# ZYNQ_DDR3.net
KiCad netlist of a schematic drawn in Altium Designer
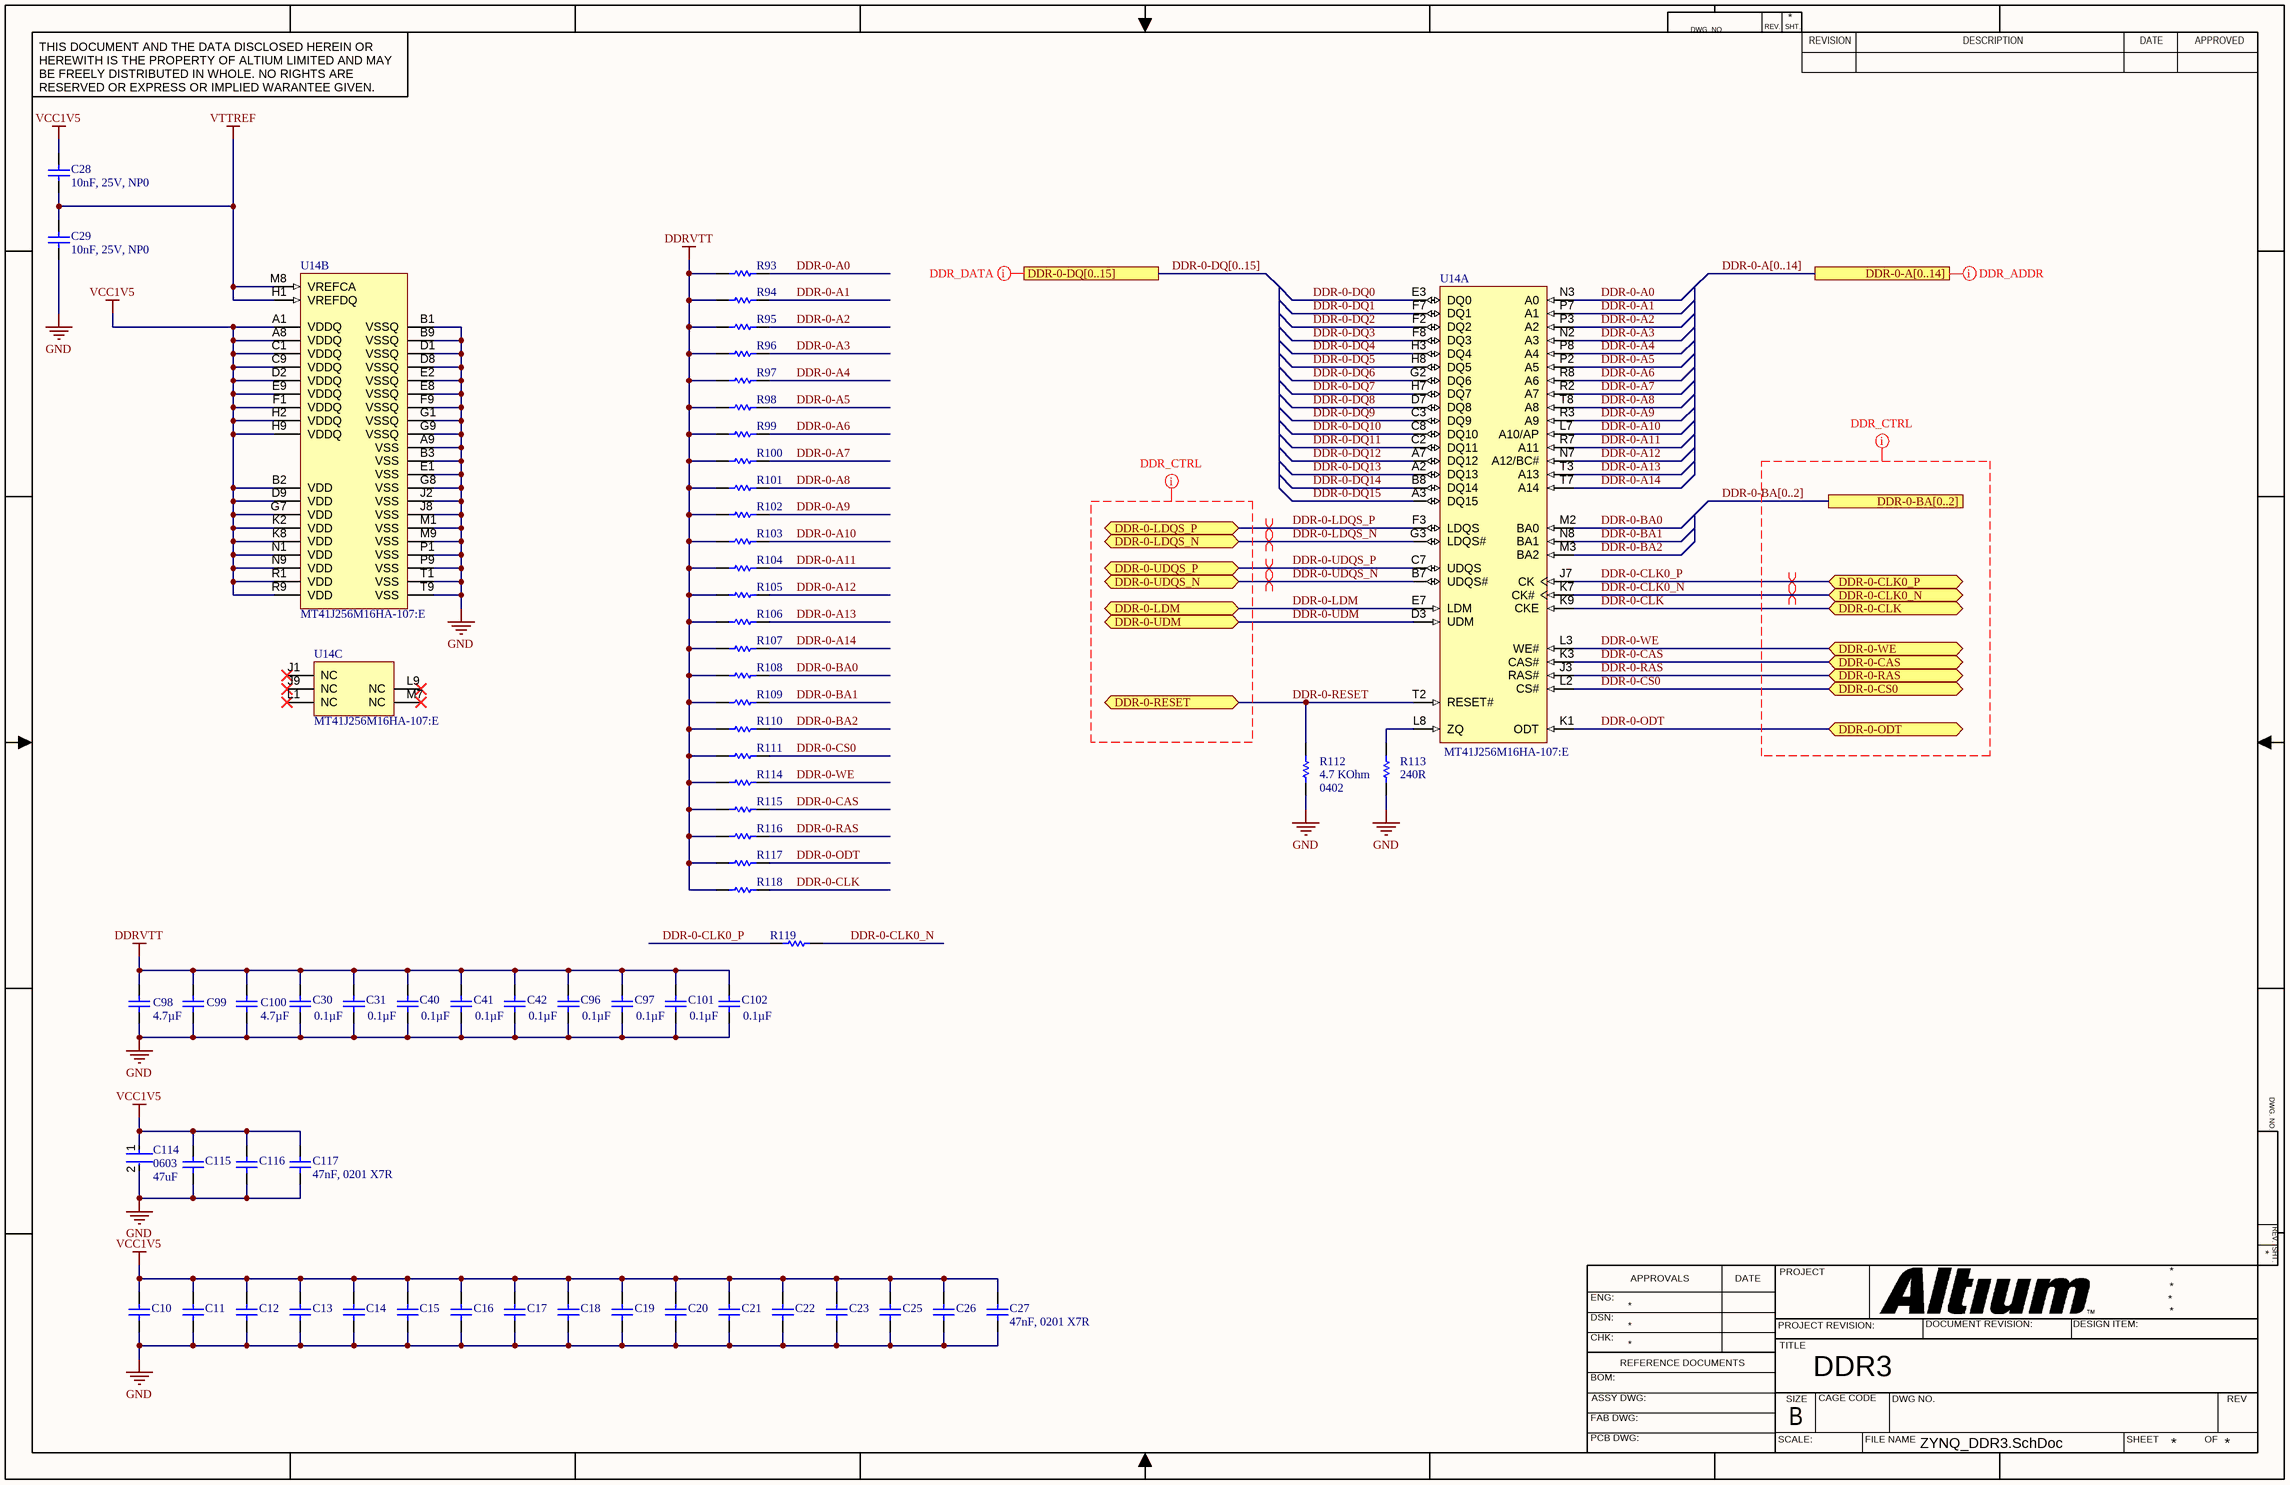
[diagram p0: ZYNQ_DDR3.SchDoc]

(export (version "E")
  (design (tool "Eeschema 10.0.6"))
  (components
    (comp (ref "C10")
      (value "~")
      (footprint "CAP0201i")
      (description "0201, 47nF, 10%, 25V, X7R")
      (libsource (lib "AmpherLib") (part "Cap_47nF_X7R_0201"))
    )
    (comp (ref "C11")
      (value "~")
      (footprint "CAP0201i")
      (description "0201, 47nF, 10%, 25V, X7R")
      (libsource (lib "AmpherLib") (part "Cap_47nF_X7R_0201"))
    )
    (comp (ref "C12")
      (value "~")
      (footprint "CAP0201i")
      (description "0201, 47nF, 10%, 25V, X7R")
      (libsource (lib "AmpherLib") (part "Cap_47nF_X7R_0201"))
    )
    (comp (ref "C13")
      (value "~")
      (footprint "CAP0201i")
      (description "0201, 47nF, 10%, 25V, X7R")
      (libsource (lib "AmpherLib") (part "Cap_47nF_X7R_0201"))
    )
    (comp (ref "C14")
      (value "~")
      (footprint "CAP0201i")
      (description "0201, 47nF, 10%, 25V, X7R")
      (libsource (lib "AmpherLib") (part "Cap_47nF_X7R_0201"))
    )
    (comp (ref "C15")
      (value "~")
      (footprint "CAP0201i")
      (description "0201, 47nF, 10%, 25V, X7R")
      (libsource (lib "AmpherLib") (part "Cap_47nF_X7R_0201"))
    )
    (comp (ref "C16")
      (value "~")
      (footprint "CAP0201i")
      (description "0201, 47nF, 10%, 25V, X7R")
      (libsource (lib "AmpherLib") (part "Cap_47nF_X7R_0201"))
    )
    (comp (ref "C17")
      (value "~")
      (footprint "CAP0201i")
      (description "0201, 47nF, 10%, 25V, X7R")
      (libsource (lib "AmpherLib") (part "Cap_47nF_X7R_0201"))
    )
    (comp (ref "C18")
      (value "~")
      (footprint "CAP0201i")
      (description "0201, 47nF, 10%, 25V, X7R")
      (libsource (lib "AmpherLib") (part "Cap_47nF_X7R_0201"))
    )
    (comp (ref "C19")
      (value "~")
      (footprint "CAP0201i")
      (description "0201, 47nF, 10%, 25V, X7R")
      (libsource (lib "AmpherLib") (part "Cap_47nF_X7R_0201"))
    )
    (comp (ref "C20")
      (value "~")
      (footprint "CAP0201i")
      (description "0201, 47nF, 10%, 25V, X7R")
      (libsource (lib "AmpherLib") (part "Cap_47nF_X7R_0201"))
    )
    (comp (ref "C21")
      (value "~")
      (footprint "CAP0201i")
      (description "0201, 47nF, 10%, 25V, X7R")
      (libsource (lib "AmpherLib") (part "Cap_47nF_X7R_0201"))
    )
    (comp (ref "C22")
      (value "~")
      (footprint "CAP0201i")
      (description "0201, 47nF, 10%, 25V, X7R")
      (libsource (lib "AmpherLib") (part "Cap_47nF_X7R_0201"))
    )
    (comp (ref "C23")
      (value "~")
      (footprint "CAP0201i")
      (description "0201, 47nF, 10%, 25V, X7R")
      (libsource (lib "AmpherLib") (part "Cap_47nF_X7R_0201"))
    )
    (comp (ref "C25")
      (value "~")
      (footprint "CAP0201i")
      (description "0201, 47nF, 10%, 25V, X7R")
      (libsource (lib "AmpherLib") (part "Cap_47nF_X7R_0201"))
    )
    (comp (ref "C26")
      (value "~")
      (footprint "CAP0201i")
      (description "0201, 47nF, 10%, 25V, X7R")
      (libsource (lib "AmpherLib") (part "Cap_47nF_X7R_0201"))
    )
    (comp (ref "C27")
      (value "47nF, 0201 X7R")
      (footprint "CAP0201i")
      (description "0201, 47nF, 10%, 25V, X7R")
      (libsource (lib "AmpherLib") (part "Cap_47nF_X7R_0201"))
    )
    (comp (ref "C28")
      (value "10nF, 25V, NP0")
      (footprint "CAP0402i")
      (description "0402,10nF,5%,25V,NP0")
      (fields (field (name "PART NUMBER") "GRM1555C1E103JE01J") (field (name "MANUFACTURER") "Murata"))
      (libsource (lib "AmpherLib") (part "Cap_10nF_25V_NP0_0402"))
    )
    (comp (ref "C29")
      (value "10nF, 25V, NP0")
      (footprint "CAP0402i")
      (description "0402,10nF,5%,25V,NP0")
      (fields (field (name "PART NUMBER") "GRM1555C1E103JE01J") (field (name "MANUFACTURER") "Murata"))
      (libsource (lib "AmpherLib") (part "Cap_10nF_25V_NP0_0402"))
    )
    (comp (ref "C30")
      (value "0.1µF")
      (footprint "CAP0402i")
      (description "0402, 0.1uF, 10%,  50V, X7R")
      (fields
        (field (name "PART NUMBER") "C1005X7R1H104K050BE")
        (field (name "VOLTAGE") "50V")
        (field (name "CAPACITANCE") "0.1µF")
      )
      (libsource (lib "AmpherLib") (part "Cap_0.1uF_50V_X7R_0402"))
    )
    (comp (ref "C31")
      (value "0.1µF")
      (footprint "CAP0402i")
      (description "0402, 0.1uF, 10%,  50V, X7R")
      (fields
        (field (name "PART NUMBER") "C1005X7R1H104K050BE")
        (field (name "VOLTAGE") "50V")
        (field (name "CAPACITANCE") "0.1µF")
      )
      (libsource (lib "AmpherLib") (part "Cap_0.1uF_50V_X7R_0402"))
    )
    (comp (ref "C40")
      (value "0.1µF")
      (footprint "CAP0402i")
      (description "0402, 0.1uF, 10%,  50V, X7R")
      (fields
        (field (name "PART NUMBER") "C1005X7R1H104K050BE")
        (field (name "VOLTAGE") "50V")
        (field (name "CAPACITANCE") "0.1µF")
      )
      (libsource (lib "AmpherLib") (part "Cap_0.1uF_50V_X7R_0402"))
    )
    (comp (ref "C41")
      (value "0.1µF")
      (footprint "CAP0402i")
      (description "0402, 0.1uF, 10%,  50V, X7R")
      (fields
        (field (name "PART NUMBER") "C1005X7R1H104K050BE")
        (field (name "VOLTAGE") "50V")
        (field (name "CAPACITANCE") "0.1µF")
      )
      (libsource (lib "AmpherLib") (part "Cap_0.1uF_50V_X7R_0402"))
    )
    (comp (ref "C42")
      (value "0.1µF")
      (footprint "CAP0402i")
      (description "0402, 0.1uF, 10%,  50V, X7R")
      (fields
        (field (name "PART NUMBER") "C1005X7R1H104K050BE")
        (field (name "VOLTAGE") "50V")
        (field (name "CAPACITANCE") "0.1µF")
      )
      (libsource (lib "AmpherLib") (part "Cap_0.1uF_50V_X7R_0402"))
    )
    (comp (ref "C96")
      (value "0.1µF")
      (footprint "CAP0402i")
      (description "0402, 0.1uF, 10%,  50V, X7R")
      (fields
        (field (name "PART NUMBER") "C1005X7R1H104K050BE")
        (field (name "VOLTAGE") "50V")
        (field (name "CAPACITANCE") "0.1µF")
      )
      (libsource (lib "AmpherLib") (part "Cap_0.1uF_50V_X7R_0402"))
    )
    (comp (ref "C97")
      (value "0.1µF")
      (footprint "CAP0402i")
      (description "0402, 0.1uF, 10%,  50V, X7R")
      (fields
        (field (name "PART NUMBER") "C1005X7R1H104K050BE")
        (field (name "VOLTAGE") "50V")
        (field (name "CAPACITANCE") "0.1µF")
      )
      (libsource (lib "AmpherLib") (part "Cap_0.1uF_50V_X7R_0402"))
    )
    (comp (ref "C98")
      (value "4.7µF")
      (footprint "CAP0402i")
      (description "CAP CER 4.7UF 10V X5R 0402")
      (fields
        (field (name "TOLERANCE") "10%")
        (field (name "CAPACITANCE") "4.7µF")
        (field (name "PART NUMBER") "C1005X5R1A475K050BC")
      )
      (libsource (lib "AmpherLib") (part "Cap_4.7uF_10V_10%_0402"))
    )
    (comp (ref "C99")
      (value "4.7µF")
      (footprint "CAP0402i")
      (description "CAP CER 4.7UF 10V X5R 0402")
      (fields (field (name "TOLERANCE") "10%") (field (name "PART NUMBER") "C1005X5R1A475K050BC"))
      (libsource (lib "AmpherLib") (part "Cap_4.7uF_10V_10%_0402"))
    )
    (comp (ref "C100")
      (value "4.7µF")
      (footprint "CAP0402i")
      (description "CAP CER 4.7UF 10V X5R 0402")
      (fields
        (field (name "TOLERANCE") "10%")
        (field (name "CAPACITANCE") "4.7µF")
        (field (name "PART NUMBER") "C1005X5R1A475K050BC")
      )
      (libsource (lib "AmpherLib") (part "Cap_4.7uF_10V_10%_0402"))
    )
    (comp (ref "C101")
      (value "0.1µF")
      (footprint "CAP0402i")
      (description "0402, 0.1uF, 10%,  50V, X7R")
      (fields
        (field (name "PART NUMBER") "C1005X7R1H104K050BE")
        (field (name "VOLTAGE") "50V")
        (field (name "CAPACITANCE") "0.1µF")
      )
      (libsource (lib "AmpherLib") (part "Cap_0.1uF_50V_X7R_0402"))
    )
    (comp (ref "C102")
      (value "0.1µF")
      (footprint "CAP0402i")
      (description "0402, 0.1uF, 10%,  50V, X7R")
      (fields
        (field (name "PART NUMBER") "C1005X7R1H104K050BE")
        (field (name "VOLTAGE") "50V")
        (field (name "CAPACITANCE") "0.1µF")
      )
      (libsource (lib "AmpherLib") (part "Cap_0.1uF_50V_X7R_0402"))
    )
    (comp (ref "C114")
      (value "GRM188R60J476ME15D")
      (footprint "FP-GRM188-0_2-IPC_B")
      (description "Chip Multilayer Ceramic Capacitors for General Purpose, 0603, 47uF, X5R, 15%, 20%, 6.3V")
      (fields
        (field (name "CASE CODE (IMPERIAL)") "0603")
        (field (name "CAPACITANCE") "47uF")
        (field (name "TOLERANCE") "20%")
      )
      (libsource (lib "Altium Content Vault") (part "11868f565c42a9108669ba33697ecf6"))
    )
    (comp (ref "C115")
      (value "4.7µF")
      (footprint "CAP0402i")
      (description "CAP CER 4.7UF 10V X5R 0402")
      (fields (field (name "TOLERANCE") "10%") (field (name "PART NUMBER") "C1005X5R1A475K050BC"))
      (libsource (lib "AmpherLib") (part "Cap_4.7uF_10V_10%_0402"))
    )
    (comp (ref "C116")
      (value "~")
      (footprint "CAP0201i")
      (description "0201, 47nF, 10%, 25V, X7R")
      (libsource (lib "AmpherLib") (part "Cap_47nF_X7R_0201"))
    )
    (comp (ref "C117")
      (value "47nF, 0201 X7R")
      (footprint "CAP0201i")
      (description "0201, 47nF, 10%, 25V, X7R")
      (libsource (lib "AmpherLib") (part "Cap_47nF_X7R_0201"))
    )
    (comp (ref "R93")
      (value "ERJ2RKF33R0X")
      (footprint "RESC1005X40X25LL05T05")
      (fields (field (name "MANUFACTURER") "Panasonic"))
      (libsource (lib "Altium Content Vault") (part "RES"))
    )
    (comp (ref "R94")
      (value "ERJ2RKF33R0X")
      (footprint "RESC1005X40X25LL05T05")
      (fields (field (name "MANUFACTURER") "Panasonic"))
      (libsource (lib "Altium Content Vault") (part "RES"))
    )
    (comp (ref "R95")
      (value "ERJ2RKF33R0X")
      (footprint "RESC1005X40X25LL05T05")
      (fields (field (name "MANUFACTURER") "Panasonic"))
      (libsource (lib "Altium Content Vault") (part "RES"))
    )
    (comp (ref "R96")
      (value "ERJ2RKF33R0X")
      (footprint "RESC1005X40X25LL05T05")
      (fields (field (name "MANUFACTURER") "Panasonic"))
      (libsource (lib "Altium Content Vault") (part "RES"))
    )
    (comp (ref "R97")
      (value "ERJ2RKF33R0X")
      (footprint "RESC1005X40X25LL05T05")
      (fields (field (name "MANUFACTURER") "Panasonic"))
      (libsource (lib "Altium Content Vault") (part "RES"))
    )
    (comp (ref "R98")
      (value "ERJ2RKF33R0X")
      (footprint "RESC1005X40X25LL05T05")
      (fields (field (name "MANUFACTURER") "Panasonic"))
      (libsource (lib "Altium Content Vault") (part "RES"))
    )
    (comp (ref "R99")
      (value "ERJ2RKF33R0X")
      (footprint "RESC1005X40X25LL05T05")
      (fields (field (name "MANUFACTURER") "Panasonic"))
      (libsource (lib "Altium Content Vault") (part "RES"))
    )
    (comp (ref "R100")
      (value "ERJ2RKF33R0X")
      (footprint "RESC1005X40X25LL05T05")
      (fields (field (name "MANUFACTURER") "Panasonic"))
      (libsource (lib "Altium Content Vault") (part "RES"))
    )
    (comp (ref "R101")
      (value "ERJ2RKF33R0X")
      (footprint "RESC1005X40X25LL05T05")
      (fields (field (name "MANUFACTURER") "Panasonic"))
      (libsource (lib "Altium Content Vault") (part "RES"))
    )
    (comp (ref "R102")
      (value "ERJ2RKF33R0X")
      (footprint "RESC1005X40X25LL05T05")
      (fields (field (name "MANUFACTURER") "Panasonic"))
      (libsource (lib "Altium Content Vault") (part "RES"))
    )
    (comp (ref "R103")
      (value "ERJ2RKF33R0X")
      (footprint "RESC1005X40X25LL05T05")
      (fields (field (name "MANUFACTURER") "Panasonic"))
      (libsource (lib "Altium Content Vault") (part "RES"))
    )
    (comp (ref "R104")
      (value "ERJ2RKF33R0X")
      (footprint "RESC1005X40X25LL05T05")
      (fields (field (name "MANUFACTURER") "Panasonic"))
      (libsource (lib "Altium Content Vault") (part "RES"))
    )
    (comp (ref "R105")
      (value "ERJ2RKF33R0X")
      (footprint "RESC1005X40X25LL05T05")
      (fields (field (name "MANUFACTURER") "Panasonic"))
      (libsource (lib "Altium Content Vault") (part "RES"))
    )
    (comp (ref "R106")
      (value "ERJ2RKF33R0X")
      (footprint "RESC1005X40X25LL05T05")
      (fields (field (name "MANUFACTURER") "Panasonic"))
      (libsource (lib "Altium Content Vault") (part "RES"))
    )
    (comp (ref "R107")
      (value "ERJ2RKF33R0X")
      (footprint "RESC1005X40X25LL05T05")
      (fields (field (name "MANUFACTURER") "Panasonic"))
      (libsource (lib "Altium Content Vault") (part "RES"))
    )
    (comp (ref "R108")
      (value "ERJ2RKF33R0X")
      (footprint "RESC1005X40X25LL05T05")
      (fields (field (name "MANUFACTURER") "Panasonic"))
      (libsource (lib "Altium Content Vault") (part "RES"))
    )
    (comp (ref "R109")
      (value "ERJ2RKF33R0X")
      (footprint "RESC1005X40X25LL05T05")
      (fields (field (name "MANUFACTURER") "Panasonic"))
      (libsource (lib "Altium Content Vault") (part "RES"))
    )
    (comp (ref "R110")
      (value "ERJ2RKF33R0X")
      (footprint "RESC1005X40X25LL05T05")
      (fields (field (name "MANUFACTURER") "Panasonic"))
      (libsource (lib "Altium Content Vault") (part "RES"))
    )
    (comp (ref "R111")
      (value "ERJ2RKF33R0X")
      (footprint "RESC1005X40X25LL05T05")
      (fields (field (name "MANUFACTURER") "Panasonic"))
      (libsource (lib "Altium Content Vault") (part "RES"))
    )
    (comp (ref "R112")
      (value "ERJ-2RKF4701X")
      (footprint "RESC1005X40X25LL05T05")
      (description "Chip Resistor, 4.7 KOhm, +/- 1%, 0.1 W, -55 to 155 degC, 0402 (1005 Metric), RoHS, Tape and Reel")
      (fields
        (field (name "RESISTANCE") "4.7 KOhm")
        (field (name "PACKAGEREFERENCE") "0402")
        (field (name "TOLERANCE") "1%")
      )
      (libsource (lib "Altium Content Vault") (part "RES-2"))
    )
    (comp (ref "R113")
      (value "240R")
      (footprint "RESC1005X40X25ML05T05")
      (description "SMD Chip Resistor, 240 Ohm, ± 1%, 63 mW, 0402 [1005 Metric], Thick Film, General Purpose")
      (fields (field (name "MANUFACTURER") "Vishay Dale") (field (name "PART NUMBER") "CRCW0402240RFKED"))
      (libsource (lib "Altium Content Vault") (part "RES"))
    )
    (comp (ref "R114")
      (value "ERJ2RKF33R0X")
      (footprint "RESC1005X40X25LL05T05")
      (fields (field (name "MANUFACTURER") "Panasonic"))
      (libsource (lib "Altium Content Vault") (part "RES"))
    )
    (comp (ref "R115")
      (value "ERJ2RKF33R0X")
      (footprint "RESC1005X40X25LL05T05")
      (fields (field (name "MANUFACTURER") "Panasonic"))
      (libsource (lib "Altium Content Vault") (part "RES"))
    )
    (comp (ref "R116")
      (value "ERJ2RKF33R0X")
      (footprint "RESC1005X40X25LL05T05")
      (fields (field (name "MANUFACTURER") "Panasonic"))
      (libsource (lib "Altium Content Vault") (part "RES"))
    )
    (comp (ref "R117")
      (value "ERJ2RKF33R0X")
      (footprint "RESC1005X40X25LL05T05")
      (fields (field (name "MANUFACTURER") "Panasonic"))
      (libsource (lib "Altium Content Vault") (part "RES"))
    )
    (comp (ref "R118")
      (value "ERJ2RKF33R0X")
      (footprint "RESC1005X40X25LL05T05")
      (fields (field (name "MANUFACTURER") "Panasonic"))
      (libsource (lib "Altium Content Vault") (part "RES"))
    )
    (comp (ref "R119")
      (value "CRCW040282R0FKED")
      (footprint "RESC1005X40X25NL05T05")
      (fields (field (name "MANUFACTURER") "Vishay Dale"))
      (libsource (lib "Altium Content Vault") (part "RES"))
    )
    (comp (ref "U14")
      (value "MT41J256M16HA-107:E")
      (footprint "MICT-HA-96")
      (description "4Gb DDR3 SDRAM, 256 Meg x 16, 1.5 V, 0 to 95 degC, 96-Ball FBGA (HA), RoHS, Tray")
      (fields (field (name "MANUFACTURER") "Micron"))
      (libsource (lib "") (part "MICT-MT41J256M16HA-96_1"))
    )
  )
  (nets
    (net (code "1") (name "/DDR-0-A0") (class "Default")
      (node (ref "R93") (pin "2") (pinfunction "2_2") (pintype "passive"))
      (node (ref "U14") (pin "N3") (pinfunction "A0_N3") (pintype "input"))
    )
    (net (code "2") (name "/DDR-0-A1") (class "Default")
      (node (ref "R94") (pin "2") (pinfunction "2_2") (pintype "passive"))
      (node (ref "U14") (pin "P7") (pinfunction "A1_P7") (pintype "input"))
    )
    (net (code "3") (name "/DDR-0-A2") (class "Default")
      (node (ref "R95") (pin "2") (pinfunction "2_2") (pintype "passive"))
      (node (ref "U14") (pin "P3") (pinfunction "A2_P3") (pintype "input"))
    )
    (net (code "4") (name "/DDR-0-A3") (class "Default")
      (node (ref "R96") (pin "2") (pinfunction "2_2") (pintype "passive"))
      (node (ref "U14") (pin "N2") (pinfunction "A3_N2") (pintype "input"))
    )
    (net (code "5") (name "/DDR-0-A4") (class "Default")
      (node (ref "R97") (pin "2") (pinfunction "2_2") (pintype "passive"))
      (node (ref "U14") (pin "P8") (pinfunction "A4_P8") (pintype "input"))
    )
    (net (code "6") (name "/DDR-0-A5") (class "Default")
      (node (ref "R98") (pin "2") (pinfunction "2_2") (pintype "passive"))
      (node (ref "U14") (pin "P2") (pinfunction "A5_P2") (pintype "input"))
    )
    (net (code "7") (name "/DDR-0-A6") (class "Default")
      (node (ref "R99") (pin "2") (pinfunction "2_2") (pintype "passive"))
      (node (ref "U14") (pin "R8") (pinfunction "A6_R8") (pintype "input"))
    )
    (net (code "8") (name "/DDR-0-A7") (class "Default")
      (node (ref "R100") (pin "2") (pinfunction "2_2") (pintype "passive"))
      (node (ref "U14") (pin "R2") (pinfunction "A7_R2") (pintype "input"))
    )
    (net (code "9") (name "/DDR-0-A8") (class "Default")
      (node (ref "R101") (pin "2") (pinfunction "2_2") (pintype "passive"))
      (node (ref "U14") (pin "T8") (pinfunction "A8_T8") (pintype "input"))
    )
    (net (code "10") (name "/DDR-0-A9") (class "Default")
      (node (ref "R102") (pin "2") (pinfunction "2_2") (pintype "passive"))
      (node (ref "U14") (pin "R3") (pinfunction "A9_R3") (pintype "input"))
    )
    (net (code "11") (name "/DDR-0-A10") (class "Default")
      (node (ref "R103") (pin "2") (pinfunction "2_2") (pintype "passive"))
      (node (ref "U14") (pin "L7") (pinfunction "A10/AP_L7") (pintype "input"))
    )
    (net (code "12") (name "/DDR-0-A11") (class "Default")
      (node (ref "R104") (pin "2") (pinfunction "2_2") (pintype "passive"))
      (node (ref "U14") (pin "R7") (pinfunction "A11_R7") (pintype "input"))
    )
    (net (code "13") (name "/DDR-0-A12") (class "Default")
      (node (ref "R105") (pin "2") (pinfunction "2_2") (pintype "passive"))
      (node (ref "U14") (pin "N7") (pinfunction "A12/BC#_N7") (pintype "input"))
    )
    (net (code "14") (name "/DDR-0-A13") (class "Default")
      (node (ref "R106") (pin "2") (pinfunction "2_2") (pintype "passive"))
      (node (ref "U14") (pin "T3") (pinfunction "A13_T3") (pintype "input"))
    )
    (net (code "15") (name "/DDR-0-A14") (class "Default")
      (node (ref "R107") (pin "2") (pinfunction "2_2") (pintype "passive"))
      (node (ref "U14") (pin "T7") (pinfunction "A14_T7") (pintype "input"))
    )
    (net (code "17") (name "/DDR-0-BA0") (class "Default")
      (node (ref "R108") (pin "2") (pinfunction "2_2") (pintype "passive"))
      (node (ref "U14") (pin "M2") (pinfunction "BA0_M2") (pintype "input"))
    )
    (net (code "18") (name "/DDR-0-BA1") (class "Default")
      (node (ref "R109") (pin "2") (pinfunction "2_2") (pintype "passive"))
      (node (ref "U14") (pin "N8") (pinfunction "BA1_N8") (pintype "input"))
    )
    (net (code "19") (name "/DDR-0-BA2") (class "Default")
      (node (ref "R110") (pin "2") (pinfunction "2_2") (pintype "passive"))
      (node (ref "U14") (pin "M3") (pinfunction "BA2_M3") (pintype "input"))
    )
    (net (code "21") (name "/DDR-0-CAS") (class "Default")
      (node (ref "R115") (pin "2") (pinfunction "2_2") (pintype "passive"))
      (node (ref "U14") (pin "K3") (pinfunction "CAS#_K3") (pintype "input"))
    )
    (net (code "22") (name "/DDR-0-CLK") (class "Default")
      (node (ref "R118") (pin "2") (pinfunction "2_2") (pintype "passive"))
      (node (ref "U14") (pin "K9") (pinfunction "CKE_K9") (pintype "input"))
    )
    (net (code "23") (name "/DDR-0-CLK0_N") (class "Default")
      (node (ref "R119") (pin "2") (pinfunction "2_2") (pintype "passive"))
      (node (ref "U14") (pin "K7") (pinfunction "CK#_K7") (pintype "input"))
    )
    (net (code "24") (name "/DDR-0-CLK0_P") (class "Default")
      (node (ref "R119") (pin "1") (pinfunction "1_1") (pintype "passive"))
      (node (ref "U14") (pin "J7") (pinfunction "CK_J7") (pintype "input"))
    )
    (net (code "25") (name "/DDR-0-CS0") (class "Default")
      (node (ref "R111") (pin "2") (pinfunction "2_2") (pintype "passive"))
      (node (ref "U14") (pin "L2") (pinfunction "CS#_L2") (pintype "input"))
    )
    (net (code "26") (name "/DDR-0-DQ0") (class "Default")
      (node (ref "U14") (pin "E3") (pinfunction "DQ0_E3") (pintype "bidirectional"))
    )
    (net (code "27") (name "/DDR-0-DQ1") (class "Default")
      (node (ref "U14") (pin "F7") (pinfunction "DQ1_F7") (pintype "bidirectional"))
    )
    (net (code "28") (name "/DDR-0-DQ2") (class "Default")
      (node (ref "U14") (pin "F2") (pinfunction "DQ2_F2") (pintype "bidirectional"))
    )
    (net (code "29") (name "/DDR-0-DQ3") (class "Default")
      (node (ref "U14") (pin "F8") (pinfunction "DQ3_F8") (pintype "bidirectional"))
    )
    (net (code "30") (name "/DDR-0-DQ4") (class "Default")
      (node (ref "U14") (pin "H3") (pinfunction "DQ4_H3") (pintype "bidirectional"))
    )
    (net (code "31") (name "/DDR-0-DQ5") (class "Default")
      (node (ref "U14") (pin "H8") (pinfunction "DQ5_H8") (pintype "bidirectional"))
    )
    (net (code "32") (name "/DDR-0-DQ6") (class "Default")
      (node (ref "U14") (pin "G2") (pinfunction "DQ6_G2") (pintype "bidirectional"))
    )
    (net (code "33") (name "/DDR-0-DQ7") (class "Default")
      (node (ref "U14") (pin "H7") (pinfunction "DQ7_H7") (pintype "bidirectional"))
    )
    (net (code "34") (name "/DDR-0-DQ8") (class "Default")
      (node (ref "U14") (pin "D7") (pinfunction "DQ8_D7") (pintype "bidirectional"))
    )
    (net (code "35") (name "/DDR-0-DQ9") (class "Default")
      (node (ref "U14") (pin "C3") (pinfunction "DQ9_C3") (pintype "bidirectional"))
    )
    (net (code "36") (name "/DDR-0-DQ10") (class "Default")
      (node (ref "U14") (pin "C8") (pinfunction "DQ10_C8") (pintype "bidirectional"))
    )
    (net (code "37") (name "/DDR-0-DQ11") (class "Default")
      (node (ref "U14") (pin "C2") (pinfunction "DQ11_C2") (pintype "bidirectional"))
    )
    (net (code "38") (name "/DDR-0-DQ12") (class "Default")
      (node (ref "U14") (pin "A7") (pinfunction "DQ12_A7") (pintype "bidirectional"))
    )
    (net (code "39") (name "/DDR-0-DQ13") (class "Default")
      (node (ref "U14") (pin "A2") (pinfunction "DQ13_A2") (pintype "bidirectional"))
    )
    (net (code "40") (name "/DDR-0-DQ14") (class "Default")
      (node (ref "U14") (pin "B8") (pinfunction "DQ14_B8") (pintype "bidirectional"))
    )
    (net (code "41") (name "/DDR-0-DQ15") (class "Default")
      (node (ref "U14") (pin "A3") (pinfunction "DQ15_A3") (pintype "bidirectional"))
    )
    (net (code "43") (name "/DDR-0-LDM") (class "Default")
      (node (ref "U14") (pin "E7") (pinfunction "LDM_E7") (pintype "input"))
    )
    (net (code "44") (name "/DDR-0-LDQS_N") (class "Default")
      (node (ref "U14") (pin "G3") (pinfunction "LDQS#_G3") (pintype "bidirectional"))
    )
    (net (code "45") (name "/DDR-0-LDQS_P") (class "Default")
      (node (ref "U14") (pin "F3") (pinfunction "LDQS_F3") (pintype "bidirectional"))
    )
    (net (code "46") (name "/DDR-0-ODT") (class "Default")
      (node (ref "R117") (pin "2") (pinfunction "2_2") (pintype "passive"))
      (node (ref "U14") (pin "K1") (pinfunction "ODT_K1") (pintype "input"))
    )
    (net (code "47") (name "/DDR-0-RAS") (class "Default")
      (node (ref "R116") (pin "2") (pinfunction "2_2") (pintype "passive"))
      (node (ref "U14") (pin "J3") (pinfunction "RAS#_J3") (pintype "input"))
    )
    (net (code "48") (name "/DDR-0-RESET") (class "Default")
      (node (ref "R112") (pin "2") (pinfunction "2_2") (pintype "passive"))
      (node (ref "U14") (pin "T2") (pinfunction "RESET#_T2") (pintype "input"))
    )
    (net (code "49") (name "/DDR-0-UDM") (class "Default")
      (node (ref "U14") (pin "D3") (pinfunction "UDM_D3") (pintype "input"))
    )
    (net (code "50") (name "/DDR-0-UDQS_N") (class "Default")
      (node (ref "U14") (pin "B7") (pinfunction "UDQS#_B7") (pintype "bidirectional"))
    )
    (net (code "51") (name "/DDR-0-UDQS_P") (class "Default")
      (node (ref "U14") (pin "C7") (pinfunction "UDQS_C7") (pintype "bidirectional"))
    )
    (net (code "52") (name "/DDR-0-WE") (class "Default")
      (node (ref "R114") (pin "2") (pinfunction "2_2") (pintype "passive"))
      (node (ref "U14") (pin "L3") (pinfunction "WE#_L3") (pintype "input"))
    )
    (net (code "53") (name "DDRVTT") (class "Default")
      (node (ref "C100") (pin "2") (pinfunction "2_2") (pintype "passive"))
      (node (ref "C101") (pin "2") (pinfunction "2_2") (pintype "passive"))
      (node (ref "C102") (pin "2") (pinfunction "2_2") (pintype "passive"))
      (node (ref "C30") (pin "2") (pinfunction "2_2") (pintype "passive"))
      (node (ref "C31") (pin "2") (pinfunction "2_2") (pintype "passive"))
      (node (ref "C40") (pin "2") (pinfunction "2_2") (pintype "passive"))
      (node (ref "C41") (pin "2") (pinfunction "2_2") (pintype "passive"))
      (node (ref "C42") (pin "2") (pinfunction "2_2") (pintype "passive"))
      (node (ref "C96") (pin "2") (pinfunction "2_2") (pintype "passive"))
      (node (ref "C97") (pin "2") (pinfunction "2_2") (pintype "passive"))
      (node (ref "C98") (pin "2") (pinfunction "2_2") (pintype "passive"))
      (node (ref "C99") (pin "2") (pinfunction "2_2") (pintype "passive"))
      (node (ref "R100") (pin "1") (pinfunction "1_1") (pintype "passive"))
      (node (ref "R101") (pin "1") (pinfunction "1_1") (pintype "passive"))
      (node (ref "R102") (pin "1") (pinfunction "1_1") (pintype "passive"))
      (node (ref "R103") (pin "1") (pinfunction "1_1") (pintype "passive"))
      (node (ref "R104") (pin "1") (pinfunction "1_1") (pintype "passive"))
      (node (ref "R105") (pin "1") (pinfunction "1_1") (pintype "passive"))
      (node (ref "R106") (pin "1") (pinfunction "1_1") (pintype "passive"))
      (node (ref "R107") (pin "1") (pinfunction "1_1") (pintype "passive"))
      (node (ref "R108") (pin "1") (pinfunction "1_1") (pintype "passive"))
      (node (ref "R109") (pin "1") (pinfunction "1_1") (pintype "passive"))
      (node (ref "R110") (pin "1") (pinfunction "1_1") (pintype "passive"))
      (node (ref "R111") (pin "1") (pinfunction "1_1") (pintype "passive"))
      (node (ref "R114") (pin "1") (pinfunction "1_1") (pintype "passive"))
      (node (ref "R115") (pin "1") (pinfunction "1_1") (pintype "passive"))
      (node (ref "R116") (pin "1") (pinfunction "1_1") (pintype "passive"))
      (node (ref "R117") (pin "1") (pinfunction "1_1") (pintype "passive"))
      (node (ref "R118") (pin "1") (pinfunction "1_1") (pintype "passive"))
      (node (ref "R93") (pin "1") (pinfunction "1_1") (pintype "passive"))
      (node (ref "R94") (pin "1") (pinfunction "1_1") (pintype "passive"))
      (node (ref "R95") (pin "1") (pinfunction "1_1") (pintype "passive"))
      (node (ref "R96") (pin "1") (pinfunction "1_1") (pintype "passive"))
      (node (ref "R97") (pin "1") (pinfunction "1_1") (pintype "passive"))
      (node (ref "R98") (pin "1") (pinfunction "1_1") (pintype "passive"))
      (node (ref "R99") (pin "1") (pinfunction "1_1") (pintype "passive"))
    )
    (net (code "54") (name "GND") (class "Default")
      (node (ref "C10") (pin "1") (pinfunction "1_1") (pintype "passive"))
      (node (ref "C100") (pin "1") (pinfunction "1_1") (pintype "passive"))
      (node (ref "C101") (pin "1") (pinfunction "1_1") (pintype "passive"))
      (node (ref "C102") (pin "1") (pinfunction "1_1") (pintype "passive"))
      (node (ref "C11") (pin "1") (pinfunction "1_1") (pintype "passive"))
      (node (ref "C114") (pin "2") (pinfunction "2_2") (pintype "passive"))
      (node (ref "C115") (pin "1") (pinfunction "1_1") (pintype "passive"))
      (node (ref "C116") (pin "1") (pinfunction "1_1") (pintype "passive"))
      (node (ref "C117") (pin "2") (pinfunction "2_2") (pintype "passive"))
      (node (ref "C12") (pin "1") (pinfunction "1_1") (pintype "passive"))
      (node (ref "C13") (pin "1") (pinfunction "1_1") (pintype "passive"))
      (node (ref "C14") (pin "1") (pinfunction "1_1") (pintype "passive"))
      (node (ref "C15") (pin "1") (pinfunction "1_1") (pintype "passive"))
      (node (ref "C16") (pin "1") (pinfunction "1_1") (pintype "passive"))
      (node (ref "C17") (pin "1") (pinfunction "1_1") (pintype "passive"))
      (node (ref "C18") (pin "1") (pinfunction "1_1") (pintype "passive"))
      (node (ref "C19") (pin "1") (pinfunction "1_1") (pintype "passive"))
      (node (ref "C20") (pin "1") (pinfunction "1_1") (pintype "passive"))
      (node (ref "C21") (pin "1") (pinfunction "1_1") (pintype "passive"))
      (node (ref "C22") (pin "1") (pinfunction "1_1") (pintype "passive"))
      (node (ref "C23") (pin "1") (pinfunction "1_1") (pintype "passive"))
      (node (ref "C25") (pin "1") (pinfunction "1_1") (pintype "passive"))
      (node (ref "C26") (pin "1") (pinfunction "1_1") (pintype "passive"))
      (node (ref "C27") (pin "1") (pinfunction "1_1") (pintype "passive"))
      (node (ref "C29") (pin "1") (pinfunction "1_1") (pintype "passive"))
      (node (ref "C30") (pin "1") (pinfunction "1_1") (pintype "passive"))
      (node (ref "C31") (pin "1") (pinfunction "1_1") (pintype "passive"))
      (node (ref "C40") (pin "1") (pinfunction "1_1") (pintype "passive"))
      (node (ref "C41") (pin "1") (pinfunction "1_1") (pintype "passive"))
      (node (ref "C42") (pin "1") (pinfunction "1_1") (pintype "passive"))
      (node (ref "C96") (pin "1") (pinfunction "1_1") (pintype "passive"))
      (node (ref "C97") (pin "1") (pinfunction "1_1") (pintype "passive"))
      (node (ref "C98") (pin "1") (pinfunction "1_1") (pintype "passive"))
      (node (ref "C99") (pin "1") (pinfunction "1_1") (pintype "passive"))
      (node (ref "R112") (pin "1") (pinfunction "1_1") (pintype "passive"))
      (node (ref "R113") (pin "1") (pinfunction "1_1") (pintype "passive"))
      (node (ref "U14") (pin "A9") (pinfunction "VSS_A9") (pintype "power_in"))
      (node (ref "U14") (pin "B1") (pinfunction "VSSQ_B1") (pintype "power_in"))
      (node (ref "U14") (pin "B3") (pinfunction "VSS_B3") (pintype "power_in"))
      (node (ref "U14") (pin "B9") (pinfunction "VSSQ_B9") (pintype "power_in"))
      (node (ref "U14") (pin "D1") (pinfunction "VSSQ_D1") (pintype "power_in"))
      (node (ref "U14") (pin "D8") (pinfunction "VSSQ_D8") (pintype "power_in"))
      (node (ref "U14") (pin "E1") (pinfunction "VSS_E1") (pintype "power_in"))
      (node (ref "U14") (pin "E2") (pinfunction "VSSQ_E2") (pintype "power_in"))
      (node (ref "U14") (pin "E8") (pinfunction "VSSQ_E8") (pintype "power_in"))
      (node (ref "U14") (pin "F9") (pinfunction "VSSQ_F9") (pintype "power_in"))
      (node (ref "U14") (pin "G1") (pinfunction "VSSQ_G1") (pintype "power_in"))
      (node (ref "U14") (pin "G8") (pinfunction "VSS_G8") (pintype "power_in"))
      (node (ref "U14") (pin "G9") (pinfunction "VSSQ_G9") (pintype "power_in"))
      (node (ref "U14") (pin "J2") (pinfunction "VSS_J2") (pintype "power_in"))
      (node (ref "U14") (pin "J8") (pinfunction "VSS_J8") (pintype "power_in"))
      (node (ref "U14") (pin "M1") (pinfunction "VSS_M1") (pintype "power_in"))
      (node (ref "U14") (pin "M9") (pinfunction "VSS_M9") (pintype "power_in"))
      (node (ref "U14") (pin "P1") (pinfunction "VSS_P1") (pintype "power_in"))
      (node (ref "U14") (pin "P9") (pinfunction "VSS_P9") (pintype "power_in"))
      (node (ref "U14") (pin "T1") (pinfunction "VSS_T1") (pintype "power_in"))
      (node (ref "U14") (pin "T9") (pinfunction "VSS_T9") (pintype "power_in"))
    )
    (net (code "55") (name "Net-(U14A-ZQ)") (class "Default")
      (node (ref "R113") (pin "2") (pinfunction "2_2") (pintype "passive"))
      (node (ref "U14") (pin "L8") (pinfunction "ZQ_L8") (pintype "input"))
    )
    (net (code "56") (name "VCC1V5") (class "Default")
      (node (ref "C10") (pin "2") (pinfunction "2_2") (pintype "passive"))
      (node (ref "C11") (pin "2") (pinfunction "2_2") (pintype "passive"))
      (node (ref "C114") (pin "1") (pinfunction "1_1") (pintype "passive"))
      (node (ref "C115") (pin "2") (pinfunction "2_2") (pintype "passive"))
      (node (ref "C116") (pin "2") (pinfunction "2_2") (pintype "passive"))
      (node (ref "C117") (pin "1") (pinfunction "1_1") (pintype "passive"))
      (node (ref "C12") (pin "2") (pinfunction "2_2") (pintype "passive"))
      (node (ref "C13") (pin "2") (pinfunction "2_2") (pintype "passive"))
      (node (ref "C14") (pin "2") (pinfunction "2_2") (pintype "passive"))
      (node (ref "C15") (pin "2") (pinfunction "2_2") (pintype "passive"))
      (node (ref "C16") (pin "2") (pinfunction "2_2") (pintype "passive"))
      (node (ref "C17") (pin "2") (pinfunction "2_2") (pintype "passive"))
      (node (ref "C18") (pin "2") (pinfunction "2_2") (pintype "passive"))
      (node (ref "C19") (pin "2") (pinfunction "2_2") (pintype "passive"))
      (node (ref "C20") (pin "2") (pinfunction "2_2") (pintype "passive"))
      (node (ref "C21") (pin "2") (pinfunction "2_2") (pintype "passive"))
      (node (ref "C22") (pin "2") (pinfunction "2_2") (pintype "passive"))
      (node (ref "C23") (pin "2") (pinfunction "2_2") (pintype "passive"))
      (node (ref "C25") (pin "2") (pinfunction "2_2") (pintype "passive"))
      (node (ref "C26") (pin "2") (pinfunction "2_2") (pintype "passive"))
      (node (ref "C27") (pin "2") (pinfunction "2_2") (pintype "passive"))
      (node (ref "C28") (pin "2") (pinfunction "2_2") (pintype "passive"))
      (node (ref "U14") (pin "A1") (pinfunction "VDDQ_A1") (pintype "power_in"))
      (node (ref "U14") (pin "A8") (pinfunction "VDDQ_A8") (pintype "power_in"))
      (node (ref "U14") (pin "B2") (pinfunction "VDD_B2") (pintype "power_in"))
      (node (ref "U14") (pin "C1") (pinfunction "VDDQ_C1") (pintype "power_in"))
      (node (ref "U14") (pin "C9") (pinfunction "VDDQ_C9") (pintype "power_in"))
      (node (ref "U14") (pin "D2") (pinfunction "VDDQ_D2") (pintype "power_in"))
      (node (ref "U14") (pin "D9") (pinfunction "VDD_D9") (pintype "power_in"))
      (node (ref "U14") (pin "E9") (pinfunction "VDDQ_E9") (pintype "power_in"))
      (node (ref "U14") (pin "F1") (pinfunction "VDDQ_F1") (pintype "power_in"))
      (node (ref "U14") (pin "G7") (pinfunction "VDD_G7") (pintype "power_in"))
      (node (ref "U14") (pin "H2") (pinfunction "VDDQ_H2") (pintype "power_in"))
      (node (ref "U14") (pin "H9") (pinfunction "VDDQ_H9") (pintype "power_in"))
      (node (ref "U14") (pin "K2") (pinfunction "VDD_K2") (pintype "power_in"))
      (node (ref "U14") (pin "K8") (pinfunction "VDD_K8") (pintype "power_in"))
      (node (ref "U14") (pin "N1") (pinfunction "VDD_N1") (pintype "power_in"))
      (node (ref "U14") (pin "N9") (pinfunction "VDD_N9") (pintype "power_in"))
      (node (ref "U14") (pin "R1") (pinfunction "VDD_R1") (pintype "power_in"))
      (node (ref "U14") (pin "R9") (pinfunction "VDD_R9") (pintype "power_in"))
    )
    (net (code "57") (name "VTTREF") (class "Default")
      (node (ref "C28") (pin "1") (pinfunction "1_1") (pintype "passive"))
      (node (ref "C29") (pin "2") (pinfunction "2_2") (pintype "passive"))
      (node (ref "U14") (pin "H1") (pinfunction "VREFDQ_H1") (pintype "input"))
      (node (ref "U14") (pin "M8") (pinfunction "VREFCA_M8") (pintype "input"))
    )
    (net (code "58") (name "unconnected-(U14C-NC-PadJ1)") (class "Default")
      (node (ref "U14") (pin "J1") (pinfunction "NC_J1") (pintype "passive+no_connect"))
    )
    (net (code "59") (name "unconnected-(U14C-NC-PadJ9)") (class "Default")
      (node (ref "U14") (pin "J9") (pinfunction "NC_J9") (pintype "passive+no_connect"))
    )
    (net (code "60") (name "unconnected-(U14C-NC-PadL1)") (class "Default")
      (node (ref "U14") (pin "L1") (pinfunction "NC_L1") (pintype "passive+no_connect"))
    )
    (net (code "61") (name "unconnected-(U14C-NC-PadL9)") (class "Default")
      (node (ref "U14") (pin "L9") (pinfunction "NC_L9") (pintype "passive+no_connect"))
    )
    (net (code "62") (name "unconnected-(U14C-NC-PadM7)") (class "Default")
      (node (ref "U14") (pin "M7") (pinfunction "NC_M7") (pintype "passive+no_connect"))
    )
  )
)
